# LCL_MCU.net
KiCad netlist of a schematic drawn in Altium Designer
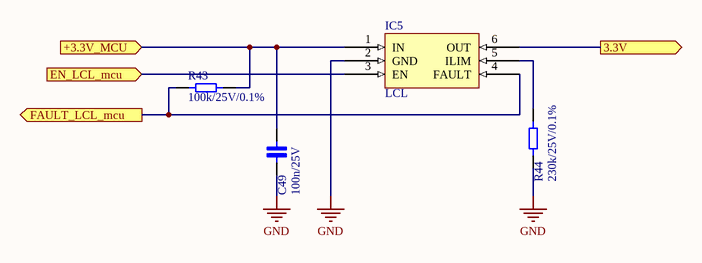
[diagram p0: LCL_MCU.SchDoc]

(export (version "E")
  (design (tool "Eeschema 10.0.6"))
  (components
    (comp (ref "C49")
      (value "100n/25V")
      (footprint "CAP_0603")
      (description "Ceramic Capacitor 100n / 0603 / 25V / ±5%, Wurth Elektronik MLCC")
      (libsource (lib "Cubesat_lib") (part "Cap_0603_100n"))
    )
    (comp (ref "IC5")
      (value "LCL")
      (footprint "SOT-23-6")
      (description "Latch-off Current Limiter")
      (libsource (lib "Cubesat_lib") (part "TPS2553"))
    )
    (comp (ref "R43")
      (value "100k/25V/0.1%")
      (footprint "RES_0603")
      (description "Vishay, thin film resistor 100k/25V/0.1%")
      (libsource (lib "Cubesat_lib") (part "Res_0603_100k"))
    )
    (comp (ref "R44")
      (value "230k/25V/0.1%")
      (footprint "RES_0603")
      (description "Vishay, thin film resistor 230k/25V/0.1%")
      (libsource (lib "Cubesat_lib") (part "Res_0603_230k"))
    )
  )
  (nets
    (net (code "1") (name "/+3.3V_MCU") (class "Default")
      (node (ref "C49") (pin "2") (pinfunction "2_2") (pintype "passive"))
      (node (ref "IC5") (pin "1") (pinfunction "IN_1") (pintype "input"))
      (node (ref "R43") (pin "2") (pinfunction "2_2") (pintype "passive"))
    )
    (net (code "2") (name "/3.3V") (class "Default")
      (node (ref "IC5") (pin "6") (pinfunction "OUT_6") (pintype "input"))
    )
    (net (code "3") (name "/EN_LCL_mcu") (class "Default")
      (node (ref "IC5") (pin "3") (pinfunction "EN_3") (pintype "input"))
    )
    (net (code "4") (name "/FAULT_LCL_mcu") (class "Default")
      (node (ref "IC5") (pin "4") (pinfunction "FAULT_4") (pintype "input"))
      (node (ref "R43") (pin "2") (pinfunction "2_2") (pintype "passive"))
    )
    (net (code "5") (name "GND") (class "Default")
      (node (ref "C49") (pin "2") (pinfunction "2_2") (pintype "passive"))
      (node (ref "IC5") (pin "2") (pinfunction "GND_2") (pintype "input"))
      (node (ref "R44") (pin "2") (pinfunction "2_2") (pintype "passive"))
    )
    (net (code "6") (name "Net-(IC5-ILIM)") (class "Default")
      (node (ref "IC5") (pin "5") (pinfunction "ILIM_5") (pintype "input"))
      (node (ref "R44") (pin "2") (pinfunction "2_2") (pintype "passive"))
    )
  )
)
